# USBload.net
KiCad netlist of a schematic drawn in EAGLE
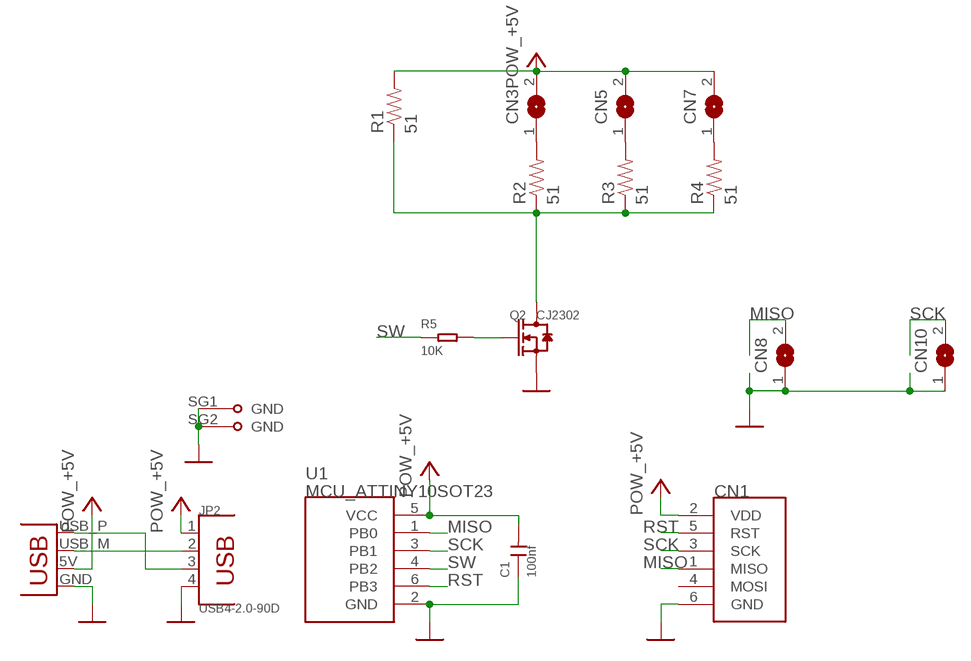
[diagram p0: schematic, sheet 1]

(export (version "E")
  (design (tool "Eeschema 10.0.6"))
  (components
    (comp (ref "C1")
      (value "100nf")
      (footprint "eagle-import:C0603")
      (fields (field (name "MPN") "CC0603KRX7R9BB104"))
      (libsource (lib "eagle-import") (part "CERAMIC-100NF-50V-10%-X7R(0603)"))
    )
    (comp (ref "CN1")
      (value "CON_AVRISPTH")
      (footprint "eagle-import:2X03R")
      (libsource (lib "eagle-import") (part "CON_AVRISPTH"))
    )
    (comp (ref "CN3")
      (value "JUMPER_SJ")
      (footprint "eagle-import:JUMPER_SJ")
      (libsource (lib "eagle-import") (part "JUMPER_SJ"))
    )
    (comp (ref "CN5")
      (value "JUMPER_SJ")
      (footprint "eagle-import:JUMPER_SJ")
      (libsource (lib "eagle-import") (part "JUMPER_SJ"))
    )
    (comp (ref "CN7")
      (value "JUMPER_SJ")
      (footprint "eagle-import:JUMPER_SJ")
      (libsource (lib "eagle-import") (part "JUMPER_SJ"))
    )
    (comp (ref "CN8")
      (value "JUMPER_SJ")
      (footprint "eagle-import:JUMPER_SJ")
      (libsource (lib "eagle-import") (part "JUMPER_SJ"))
    )
    (comp (ref "CN10")
      (value "JUMPER_SJ")
      (footprint "eagle-import:JUMPER_SJ")
      (libsource (lib "eagle-import") (part "JUMPER_SJ"))
    )
    (comp (ref "JP1")
      (value "CON_USBPCB")
      (footprint "eagle-import:USB-A-PCB")
      (libsource (lib "eagle-import") (part "CON_USBPCB"))
    )
    (comp (ref "JP2")
      (value "USB4-2.0-90D")
      (footprint "eagle-import:USB4+2P-2.0-90D")
      (libsource (lib "eagle-import") (part "DIP-USB-A-TYPE-FMAL(4+2P-2.0-90D)"))
    )
    (comp (ref "Q2")
      (value "CJ2302")
      (footprint "eagle-import:SOT-23")
      (libsource (lib "eagle-import") (part "SMD-MOSFET-N-CH-20V-2.1A-CJ2302(SOT-23)"))
    )
    (comp (ref "R1")
      (value "51")
      (footprint "eagle-import:0805")
      (libsource (lib "eagle-import") (part "RES0805"))
    )
    (comp (ref "R2")
      (value "51")
      (footprint "eagle-import:0805")
      (libsource (lib "eagle-import") (part "RES0805"))
    )
    (comp (ref "R3")
      (value "51")
      (footprint "eagle-import:0805")
      (libsource (lib "eagle-import") (part "RES0805"))
    )
    (comp (ref "R4")
      (value "51")
      (footprint "eagle-import:0805")
      (libsource (lib "eagle-import") (part "RES0805"))
    )
    (comp (ref "R5")
      (value "10K")
      (footprint "eagle-import:R0603")
      (fields (field (name "MPN") "RC0603FR-0710KL"))
      (libsource (lib "eagle-import") (part "SMD-RES-10K-1%-1/10W(0603)"))
    )
    (comp (ref "U1")
      (value "MCU_ATTINY10SOT23")
      (footprint "eagle-import:SOT23-6")
      (libsource (lib "eagle-import") (part "MCU_ATTINY10SOT23"))
    )
  )
  (nets
    (net (code "1") (name "/MISO") (class "Default")
      (node (ref "CN1") (pin "1") (pinfunction "MISO_1") (pintype "bidirectional"))
      (node (ref "CN8") (pin "2") (pinfunction "2_2") (pintype "passive"))
      (node (ref "U1") (pin "1") (pinfunction "PB0_1") (pintype "bidirectional"))
    )
    (net (code "2") (name "/RST") (class "Default")
      (node (ref "CN1") (pin "5") (pinfunction "RST_5") (pintype "bidirectional"))
      (node (ref "U1") (pin "6") (pinfunction "PB3_6") (pintype "bidirectional"))
    )
    (net (code "3") (name "/SCK") (class "Default")
      (node (ref "CN1") (pin "3") (pinfunction "SCK_3") (pintype "bidirectional"))
      (node (ref "CN10") (pin "2") (pinfunction "2_2") (pintype "passive"))
      (node (ref "U1") (pin "3") (pinfunction "PB1_3") (pintype "bidirectional"))
    )
    (net (code "4") (name "/SW") (class "Default")
      (node (ref "R5") (pin "1") (pinfunction "1_1") (pintype "passive"))
      (node (ref "U1") (pin "4") (pinfunction "PB2_4") (pintype "bidirectional"))
    )
    (net (code "5") (name "Net-(CN3-Pad1)") (class "Default")
      (node (ref "CN3") (pin "1") (pinfunction "1_1") (pintype "passive"))
      (node (ref "R2") (pin "2") (pinfunction "2_2") (pintype "passive"))
    )
    (net (code "6") (name "Net-(CN5-Pad1)") (class "Default")
      (node (ref "CN5") (pin "1") (pinfunction "1_1") (pintype "passive"))
      (node (ref "R3") (pin "2") (pinfunction "2_2") (pintype "passive"))
    )
    (net (code "7") (name "Net-(CN7-Pad1)") (class "Default")
      (node (ref "CN7") (pin "1") (pinfunction "1_1") (pintype "passive"))
      (node (ref "R4") (pin "2") (pinfunction "2_2") (pintype "passive"))
    )
    (net (code "8") (name "Net-(JP1-D+)") (class "Default")
      (node (ref "JP1") (pin "USB_P") (pinfunction "D+_USB_P") (pintype "bidirectional"))
      (node (ref "JP2") (pin "3") (pinfunction "3_3") (pintype "bidirectional"))
    )
    (net (code "9") (name "Net-(JP1-D-)") (class "Default")
      (node (ref "JP1") (pin "USB_M") (pinfunction "D-_USB_M") (pintype "bidirectional"))
      (node (ref "JP2") (pin "2") (pinfunction "2_2") (pintype "bidirectional"))
    )
    (net (code "10") (name "Net-(Q2-D)") (class "Default")
      (node (ref "Q2") (pin "3") (pinfunction "D_3") (pintype "passive"))
      (node (ref "R1") (pin "1") (pinfunction "1_1") (pintype "passive"))
      (node (ref "R2") (pin "1") (pinfunction "1_1") (pintype "passive"))
      (node (ref "R3") (pin "1") (pinfunction "1_1") (pintype "passive"))
      (node (ref "R4") (pin "1") (pinfunction "1_1") (pintype "passive"))
    )
    (net (code "11") (name "Net-(Q2-G)") (class "Default")
      (node (ref "Q2") (pin "1") (pinfunction "G_1") (pintype "passive"))
      (node (ref "R5") (pin "2") (pinfunction "2_2") (pintype "passive"))
    )
    (net (code "12") (name "POW_+5V") (class "Default")
      (node (ref "C1") (pin "2") (pinfunction "2_2") (pintype "passive"))
      (node (ref "CN1") (pin "2") (pinfunction "VDD_2") (pintype "bidirectional"))
      (node (ref "CN3") (pin "2") (pinfunction "2_2") (pintype "passive"))
      (node (ref "CN5") (pin "2") (pinfunction "2_2") (pintype "passive"))
      (node (ref "CN7") (pin "2") (pinfunction "2_2") (pintype "passive"))
      (node (ref "JP1") (pin "5V") (pinfunction "VBUS_5V") (pintype "bidirectional"))
      (node (ref "JP2") (pin "1") (pinfunction "1_1") (pintype "bidirectional"))
      (node (ref "R1") (pin "2") (pinfunction "2_2") (pintype "passive"))
      (node (ref "U1") (pin "5") (pinfunction "VCC_5") (pintype "bidirectional"))
    )
    (net (code "13") (name "POW_GND") (class "Default")
      (node (ref "C1") (pin "1") (pinfunction "1_1") (pintype "passive"))
      (node (ref "CN1") (pin "6") (pinfunction "GND_6") (pintype "bidirectional"))
      (node (ref "CN10") (pin "1") (pinfunction "1_1") (pintype "passive"))
      (node (ref "CN8") (pin "1") (pinfunction "1_1") (pintype "passive"))
      (node (ref "JP1") (pin "GND") (pinfunction "GND_GND") (pintype "bidirectional"))
      (node (ref "JP2") (pin "4") (pinfunction "4_4") (pintype "bidirectional"))
      (node (ref "JP2") (pin "SG1") (pinfunction "GND_SG1") (pintype "passive"))
      (node (ref "JP2") (pin "SG2") (pinfunction "GND_SG2") (pintype "passive"))
      (node (ref "Q2") (pin "2") (pinfunction "S_2") (pintype "passive"))
      (node (ref "U1") (pin "2") (pinfunction "GND_2") (pintype "bidirectional"))
    )
    (net (code "14") (name "unconnected-(CN1-MOSI-Pad4)") (class "Default")
      (node (ref "CN1") (pin "4") (pinfunction "MOSI_4") (pintype "bidirectional"))
    )
  )
)
